# KammsensorV1.net
KiCad netlist of a schematic drawn in EAGLE
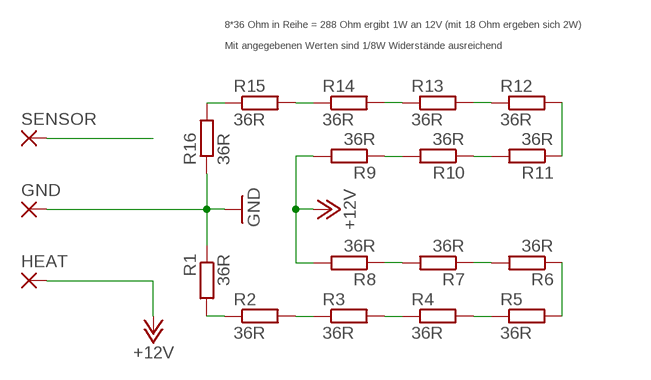
[diagram p0: schematic, sheet 1]

(export (version "E")
  (design (tool "Eeschema 10.0.6"))
  (components
    (comp (ref "GND")
      (value "WIREPADSMD5-1,8")
      (footprint "eagle-import:5-1,8")
      (libsource (lib "eagle-import") (part "WIREPADSMD5-1,8"))
    )
    (comp (ref "HEAT")
      (value "WIREPADSMD5-1,8")
      (footprint "eagle-import:5-1,8")
      (libsource (lib "eagle-import") (part "WIREPADSMD5-1,8"))
    )
    (comp (ref "R1")
      (value "36R")
      (footprint "eagle-import:M1206")
      (libsource (lib "eagle-import") (part "R-EU_M1206"))
    )
    (comp (ref "R2")
      (value "36R")
      (footprint "eagle-import:M1206")
      (libsource (lib "eagle-import") (part "R-EU_M1206"))
    )
    (comp (ref "R3")
      (value "36R")
      (footprint "eagle-import:M1206")
      (libsource (lib "eagle-import") (part "R-EU_M1206"))
    )
    (comp (ref "R4")
      (value "36R")
      (footprint "eagle-import:M1206")
      (libsource (lib "eagle-import") (part "R-EU_M1206"))
    )
    (comp (ref "R5")
      (value "36R")
      (footprint "eagle-import:M1206")
      (libsource (lib "eagle-import") (part "R-EU_M1206"))
    )
    (comp (ref "R6")
      (value "36R")
      (footprint "eagle-import:M1206")
      (libsource (lib "eagle-import") (part "R-EU_M1206"))
    )
    (comp (ref "R7")
      (value "36R")
      (footprint "eagle-import:M1206")
      (libsource (lib "eagle-import") (part "R-EU_M1206"))
    )
    (comp (ref "R8")
      (value "36R")
      (footprint "eagle-import:M1206")
      (libsource (lib "eagle-import") (part "R-EU_M1206"))
    )
    (comp (ref "R9")
      (value "36R")
      (footprint "eagle-import:M1206")
      (libsource (lib "eagle-import") (part "R-EU_M1206"))
    )
    (comp (ref "R10")
      (value "36R")
      (footprint "eagle-import:M1206")
      (libsource (lib "eagle-import") (part "R-EU_M1206"))
    )
    (comp (ref "R11")
      (value "36R")
      (footprint "eagle-import:M1206")
      (libsource (lib "eagle-import") (part "R-EU_M1206"))
    )
    (comp (ref "R12")
      (value "36R")
      (footprint "eagle-import:M1206")
      (libsource (lib "eagle-import") (part "R-EU_M1206"))
    )
    (comp (ref "R13")
      (value "36R")
      (footprint "eagle-import:M1206")
      (libsource (lib "eagle-import") (part "R-EU_M1206"))
    )
    (comp (ref "R14")
      (value "36R")
      (footprint "eagle-import:M1206")
      (libsource (lib "eagle-import") (part "R-EU_M1206"))
    )
    (comp (ref "R15")
      (value "36R")
      (footprint "eagle-import:M1206")
      (libsource (lib "eagle-import") (part "R-EU_M1206"))
    )
    (comp (ref "R16")
      (value "36R")
      (footprint "eagle-import:M1206")
      (libsource (lib "eagle-import") (part "R-EU_M1206"))
    )
    (comp (ref "SENSOR")
      (value "WIREPADSMD5-1,8")
      (footprint "eagle-import:5-1,8")
      (libsource (lib "eagle-import") (part "WIREPADSMD5-1,8"))
    )
  )
  (nets
    (net (code "1") (name "+12V") (class "Default")
      (node (ref "HEAT") (pin "1") (pinfunction "P_1") (pintype "passive"))
      (node (ref "R8") (pin "2") (pinfunction "2_2") (pintype "passive"))
      (node (ref "R9") (pin "2") (pinfunction "2_2") (pintype "passive"))
    )
    (net (code "2") (name "GND") (class "Default")
      (node (ref "GND") (pin "1") (pinfunction "P_1") (pintype "passive"))
      (node (ref "R1") (pin "1") (pinfunction "1_1") (pintype "passive"))
      (node (ref "R16") (pin "1") (pinfunction "1_1") (pintype "passive"))
    )
    (net (code "3") (name "Net-(R1-Pad2)") (class "Default")
      (node (ref "R1") (pin "2") (pinfunction "2_2") (pintype "passive"))
      (node (ref "R2") (pin "1") (pinfunction "1_1") (pintype "passive"))
    )
    (net (code "4") (name "Net-(R2-Pad2)") (class "Default")
      (node (ref "R2") (pin "2") (pinfunction "2_2") (pintype "passive"))
      (node (ref "R3") (pin "1") (pinfunction "1_1") (pintype "passive"))
    )
    (net (code "5") (name "Net-(R3-Pad2)") (class "Default")
      (node (ref "R3") (pin "2") (pinfunction "2_2") (pintype "passive"))
      (node (ref "R4") (pin "1") (pinfunction "1_1") (pintype "passive"))
    )
    (net (code "6") (name "Net-(R4-Pad2)") (class "Default")
      (node (ref "R4") (pin "2") (pinfunction "2_2") (pintype "passive"))
      (node (ref "R5") (pin "1") (pinfunction "1_1") (pintype "passive"))
    )
    (net (code "7") (name "Net-(R5-Pad2)") (class "Default")
      (node (ref "R5") (pin "2") (pinfunction "2_2") (pintype "passive"))
      (node (ref "R6") (pin "1") (pinfunction "1_1") (pintype "passive"))
    )
    (net (code "8") (name "Net-(R6-Pad2)") (class "Default")
      (node (ref "R6") (pin "2") (pinfunction "2_2") (pintype "passive"))
      (node (ref "R7") (pin "1") (pinfunction "1_1") (pintype "passive"))
    )
    (net (code "9") (name "Net-(R7-Pad2)") (class "Default")
      (node (ref "R7") (pin "2") (pinfunction "2_2") (pintype "passive"))
      (node (ref "R8") (pin "1") (pinfunction "1_1") (pintype "passive"))
    )
    (net (code "10") (name "Net-(R10-Pad1)") (class "Default")
      (node (ref "R10") (pin "1") (pinfunction "1_1") (pintype "passive"))
      (node (ref "R11") (pin "2") (pinfunction "2_2") (pintype "passive"))
    )
    (net (code "11") (name "Net-(R10-Pad2)") (class "Default")
      (node (ref "R10") (pin "2") (pinfunction "2_2") (pintype "passive"))
      (node (ref "R9") (pin "1") (pinfunction "1_1") (pintype "passive"))
    )
    (net (code "12") (name "Net-(R11-Pad1)") (class "Default")
      (node (ref "R11") (pin "1") (pinfunction "1_1") (pintype "passive"))
      (node (ref "R12") (pin "2") (pinfunction "2_2") (pintype "passive"))
    )
    (net (code "13") (name "Net-(R12-Pad1)") (class "Default")
      (node (ref "R12") (pin "1") (pinfunction "1_1") (pintype "passive"))
      (node (ref "R13") (pin "2") (pinfunction "2_2") (pintype "passive"))
    )
    (net (code "14") (name "Net-(R13-Pad1)") (class "Default")
      (node (ref "R13") (pin "1") (pinfunction "1_1") (pintype "passive"))
      (node (ref "R14") (pin "2") (pinfunction "2_2") (pintype "passive"))
    )
    (net (code "15") (name "Net-(R14-Pad1)") (class "Default")
      (node (ref "R14") (pin "1") (pinfunction "1_1") (pintype "passive"))
      (node (ref "R15") (pin "2") (pinfunction "2_2") (pintype "passive"))
    )
    (net (code "16") (name "Net-(R15-Pad1)") (class "Default")
      (node (ref "R15") (pin "1") (pinfunction "1_1") (pintype "passive"))
      (node (ref "R16") (pin "2") (pinfunction "2_2") (pintype "passive"))
    )
    (net (code "17") (name "unconnected-(SENSOR-P-Pad1)") (class "Default")
      (node (ref "SENSOR") (pin "1") (pinfunction "P_1") (pintype "passive"))
    )
  )
)
